# Tx_power.net
KiCad netlist of a schematic drawn in Altium Designer
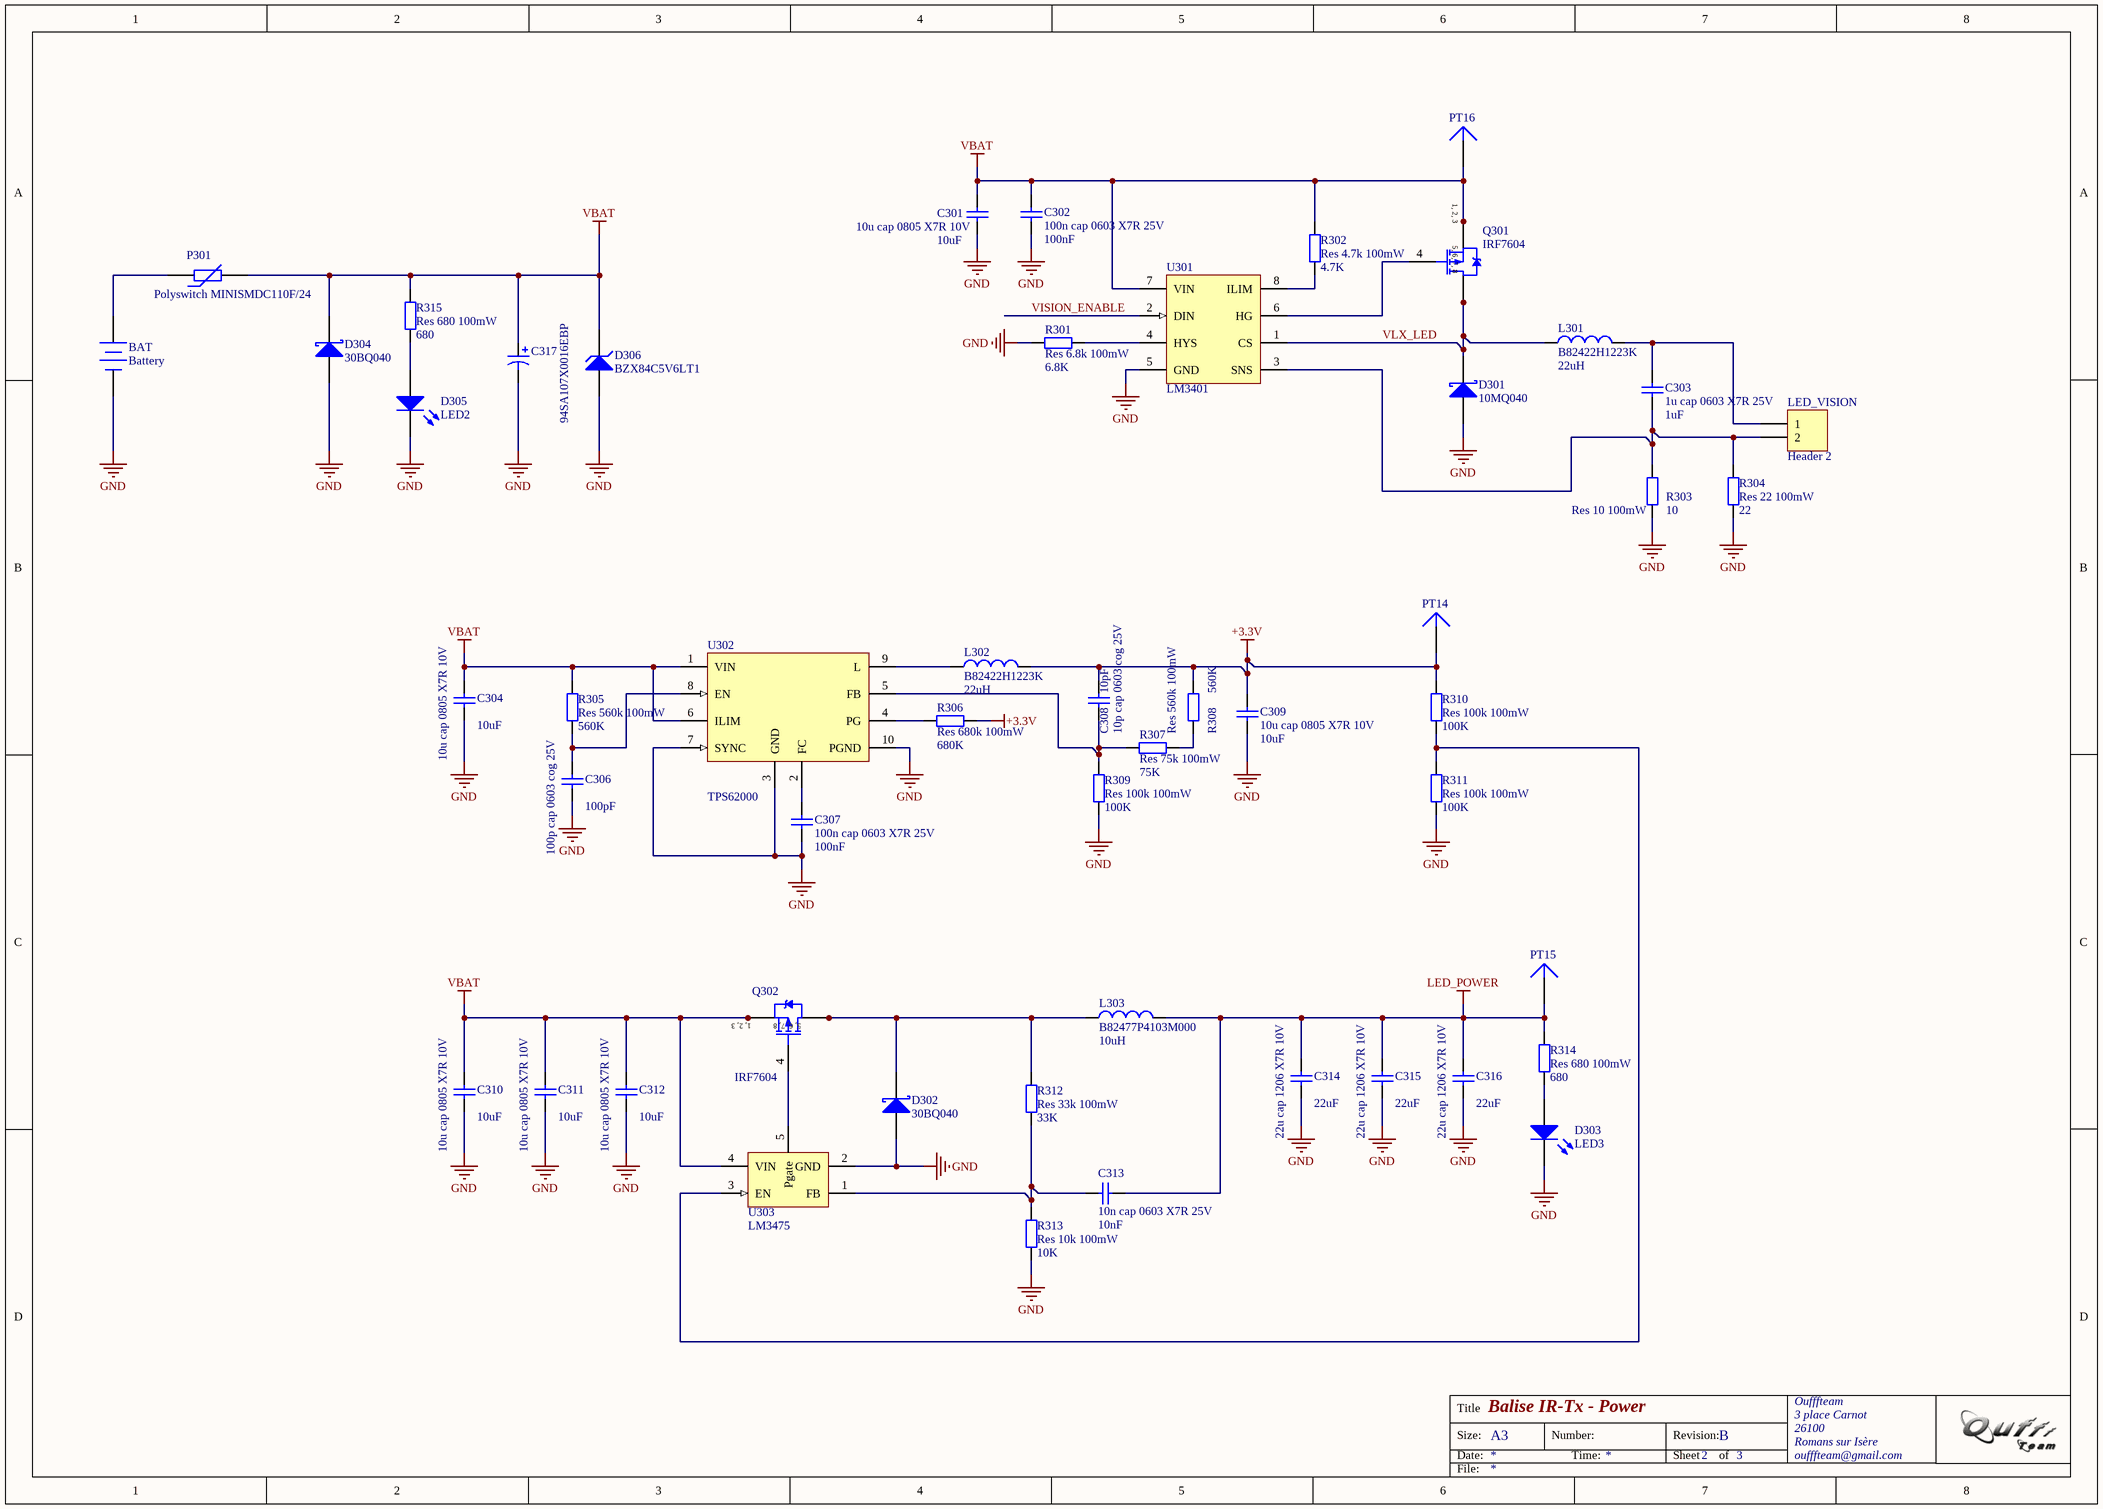
[diagram p0: Tx_power.SchDoc]

(export (version "E")
  (design (tool "Eeschema 10.0.6"))
  (components
    (comp (ref "BAT")
      (value "Battery")
      (footprint "BAT-2")
      (description "Multicell Battery")
      (fields (field (name "PUBLISHER") "Altium Limited"))
      (libsource (lib "Miscellaneous Devices") (part "Battery"))
    )
    (comp (ref "C301")
      (value "10u cap 0805 X7R 10V")
      (footprint "0805")
      (description "Capacitor")
      (fields (field (name "ALTIUM_VALUE") "10uF") (field (name "PUBLISHER") "Altium Limited"))
      (libsource (lib "Miscellaneous Devices") (part "Cap"))
    )
    (comp (ref "C302")
      (value "100n cap 0603 X7R 25V")
      (footprint "0603")
      (description "Capacitor")
      (fields (field (name "ALTIUM_VALUE") "100nF") (field (name "PUBLISHER") "Altium Limited"))
      (libsource (lib "Miscellaneous Devices") (part "Cap"))
    )
    (comp (ref "C303")
      (value "1u cap 0603 X7R 25V")
      (footprint "0603")
      (description "Capacitor")
      (fields (field (name "ALTIUM_VALUE") "1uF") (field (name "PUBLISHER") "Altium Limited"))
      (libsource (lib "Miscellaneous Devices") (part "Cap"))
    )
    (comp (ref "C304")
      (value "10u cap 0805 X7R 10V")
      (footprint "0805")
      (description "Capacitor")
      (fields (field (name "ALTIUM_VALUE") "10uF") (field (name "PUBLISHER") "Altium Limited"))
      (libsource (lib "Miscellaneous Devices") (part "Cap"))
    )
    (comp (ref "C306")
      (value "100p cap 0603 cog 25V")
      (footprint "0603")
      (description "Capacitor")
      (fields (field (name "ALTIUM_VALUE") "100pF") (field (name "PUBLISHER") "Altium Limited"))
      (libsource (lib "Miscellaneous Devices") (part "Cap"))
    )
    (comp (ref "C307")
      (value "100n cap 0603 X7R 25V")
      (footprint "0603")
      (description "Capacitor")
      (fields (field (name "ALTIUM_VALUE") "100nF") (field (name "PUBLISHER") "Altium Limited"))
      (libsource (lib "Miscellaneous Devices") (part "Cap"))
    )
    (comp (ref "C308")
      (value "10p cap 0603 cog 25V")
      (footprint "0603")
      (description "Capacitor")
      (fields (field (name "ALTIUM_VALUE") "10pF") (field (name "PUBLISHER") "Altium Limited"))
      (libsource (lib "Miscellaneous Devices") (part "Cap"))
    )
    (comp (ref "C309")
      (value "10u cap 0805 X7R 10V")
      (footprint "0805")
      (description "Capacitor")
      (fields (field (name "ALTIUM_VALUE") "10uF") (field (name "PUBLISHER") "Altium Limited"))
      (libsource (lib "Miscellaneous Devices") (part "Cap"))
    )
    (comp (ref "C310")
      (value "10u cap 0805 X7R 10V")
      (footprint "0805")
      (description "Capacitor")
      (fields (field (name "ALTIUM_VALUE") "10uF") (field (name "PUBLISHER") "Altium Limited"))
      (libsource (lib "Miscellaneous Devices") (part "Cap"))
    )
    (comp (ref "C311")
      (value "10u cap 0805 X7R 10V")
      (footprint "0805")
      (description "Capacitor")
      (fields (field (name "ALTIUM_VALUE") "10uF") (field (name "PUBLISHER") "Altium Limited"))
      (libsource (lib "Miscellaneous Devices") (part "Cap"))
    )
    (comp (ref "C312")
      (value "10u cap 0805 X7R 10V")
      (footprint "0805")
      (description "Capacitor")
      (fields (field (name "ALTIUM_VALUE") "10uF") (field (name "PUBLISHER") "Altium Limited"))
      (libsource (lib "Miscellaneous Devices") (part "Cap"))
    )
    (comp (ref "C313")
      (value "10n cap 0603 X7R 25V")
      (footprint "0603")
      (description "Capacitor")
      (fields (field (name "ALTIUM_VALUE") "10nF") (field (name "PUBLISHER") "Altium Limited"))
      (libsource (lib "Miscellaneous Devices") (part "Cap"))
    )
    (comp (ref "C314")
      (value "22u cap 1206 X7R 10V")
      (footprint "1206")
      (description "Capacitor")
      (fields (field (name "ALTIUM_VALUE") "22uF") (field (name "PUBLISHER") "Altium Limited"))
      (libsource (lib "Miscellaneous Devices") (part "Cap"))
    )
    (comp (ref "C315")
      (value "22u cap 1206 X7R 10V")
      (footprint "1206")
      (description "Capacitor")
      (fields (field (name "ALTIUM_VALUE") "22uF") (field (name "PUBLISHER") "Altium Limited"))
      (libsource (lib "Miscellaneous Devices") (part "Cap"))
    )
    (comp (ref "C316")
      (value "22u cap 1206 X7R 10V")
      (footprint "1206")
      (description "Capacitor")
      (fields (field (name "ALTIUM_VALUE") "22uF") (field (name "PUBLISHER") "Altium Limited"))
      (libsource (lib "Miscellaneous Devices") (part "Cap"))
    )
    (comp (ref "C317")
      (value "94SA107X0016EBP")
      (footprint "E")
      (description "Solid Aluminum Capacitor with Organic Semiconductor Electrolyte: 100uF, 16V, Bulk Pack")
      (fields (field (name "PUBLISHER") "Altium Limited"))
      (libsource (lib "Vishay Electrolytic Radial-Lead Capacitor") (part "94SA107X0016EBP"))
    )
    (comp (ref "D301")
      (value "10MQ040")
      (footprint "D-64")
      (description "Schottky Rectifier")
      (fields (field (name "PUBLISHER") "Altium Limited"))
      (libsource (lib "IR Rectifier - Schottky") (part "10MQ040"))
    )
    (comp (ref "D302")
      (value "30BQ040")
      (footprint "SMC")
      (description "Schottky Rectifier")
      (fields (field (name "PUBLISHER") "Altium Limited"))
      (libsource (lib "IR Rectifier - Schottky") (part "30BQ040"))
    )
    (comp (ref "D303")
      (value "LED3")
      (footprint "0603")
      (description "Typical BLUE SiC LED")
      (fields (field (name "PUBLISHER") "Altium Limited"))
      (libsource (lib "Miscellaneous Devices") (part "LED3"))
    )
    (comp (ref "D304")
      (value "30BQ040")
      (footprint "SMC")
      (description "Schottky Rectifier")
      (fields (field (name "PUBLISHER") "Altium Limited"))
      (libsource (lib "IR Rectifier - Schottky") (part "30BQ040"))
    )
    (comp (ref "D305")
      (value "LED2")
      (footprint "0603")
      (description "Typical RED, GREEN, YELLOW, AMBER GaAs LED")
      (fields (field (name "PUBLISHER") "Altium Limited"))
      (libsource (lib "Miscellaneous Devices") (part "LED2"))
    )
    (comp (ref "D306")
      (value "BZX84C5V6LT1")
      (footprint "318-07")
      (description "Zener Voltage Regulator Diode")
      (fields (field (name "PUBLISHER") "Altium Limited"))
      (libsource (lib "Motorola Discrete Diode") (part "BZX84C5V6LT1"))
    )
    (comp (ref "L301")
      (value "B82422H1223K")
      (footprint "1210")
      (description "Inductor")
      (fields (field (name "ALTIUM_VALUE") "22uH") (field (name "PUBLISHER") "Altium Limited"))
      (libsource (lib "Miscellaneous Devices") (part "Inductor"))
    )
    (comp (ref "L302")
      (value "B82422H1223K")
      (footprint "1210")
      (description "Inductor")
      (fields (field (name "ALTIUM_VALUE") "22uH") (field (name "PUBLISHER") "Altium Limited"))
      (libsource (lib "Miscellaneous Devices") (part "Inductor"))
    )
    (comp (ref "L303")
      (value "B82477P4103M000")
      (footprint "B82477P4103M000")
      (description "Inductor")
      (fields (field (name "ALTIUM_VALUE") "10uH") (field (name "PUBLISHER") "Altium Limited"))
      (libsource (lib "Miscellaneous Devices") (part "Inductor"))
    )
    (comp (ref "LED_VISION")
      (value "Header 2")
      (footprint "HDR1X2")
      (description "Header, 2-Pin")
      (fields (field (name "PUBLISHER") "Altium Limited"))
      (libsource (lib "Miscellaneous Connectors") (part "Header 2"))
    )
    (comp (ref "P301")
      (value "Polyswitch MINISMDC110F/24")
      (footprint "1812")
      (description "Varistor (Voltage-Sensitive Resistor)")
      (fields (field (name "PUBLISHER") "Altium Limited"))
      (libsource (lib "Miscellaneous Devices") (part "Res Varistor"))
    )
    (comp (ref "PT14")
      (value "Plug")
      (footprint "TP")
      (fields (field (name "PUBLISHER") "Altium Limited"))
      (libsource (lib "Miscellaneous Connectors") (part "Plug"))
    )
    (comp (ref "PT15")
      (value "Plug")
      (footprint "TP")
      (fields (field (name "PUBLISHER") "Altium Limited"))
      (libsource (lib "Miscellaneous Connectors") (part "Plug"))
    )
    (comp (ref "PT16")
      (value "Plug")
      (footprint "TP")
      (fields (field (name "PUBLISHER") "Altium Limited"))
      (libsource (lib "Miscellaneous Connectors") (part "Plug"))
    )
    (comp (ref "Q301")
      (value "IRF7604")
      (footprint "Micro8")
      (description "HEXFET Power MOSFET")
      (fields (field (name "PUBLISHER") "Altium Limited"))
      (libsource (lib "IR Discrete MOSFET - Power") (part "IRF7604"))
    )
    (comp (ref "Q302")
      (value "IRF7604")
      (footprint "Micro8")
      (description "HEXFET Power MOSFET")
      (fields (field (name "PUBLISHER") "Altium Limited"))
      (libsource (lib "IR Discrete MOSFET - Power") (part "IRF7604"))
    )
    (comp (ref "R301")
      (value "Res 6.8k 100mW")
      (footprint "0603")
      (description "Resistor")
      (fields (field (name "ALTIUM_VALUE") "6.8K") (field (name "PUBLISHER") "Altium Limited"))
      (libsource (lib "") (part "Res2_1"))
    )
    (comp (ref "R302")
      (value "Res 4.7k 100mW")
      (footprint "0603")
      (description "Resistor")
      (fields (field (name "ALTIUM_VALUE") "4.7K") (field (name "PUBLISHER") "Altium Limited"))
      (libsource (lib "Miscellaneous Devices") (part "Res2"))
    )
    (comp (ref "R303")
      (value "Res 10 100mW")
      (footprint "0603")
      (description "Resistor")
      (fields (field (name "ALTIUM_VALUE") "10") (field (name "PUBLISHER") "Altium Limited"))
      (libsource (lib "Miscellaneous Devices") (part "Res2"))
    )
    (comp (ref "R304")
      (value "Res 22 100mW")
      (footprint "0603")
      (description "Resistor")
      (fields (field (name "ALTIUM_VALUE") "22") (field (name "PUBLISHER") "Altium Limited"))
      (libsource (lib "Miscellaneous Devices") (part "Res2"))
    )
    (comp (ref "R305")
      (value "Res 560k 100mW")
      (footprint "0603")
      (description "Resistor")
      (fields (field (name "ALTIUM_VALUE") "560K") (field (name "PUBLISHER") "Altium Limited"))
      (libsource (lib "Miscellaneous Devices") (part "Res2"))
    )
    (comp (ref "R306")
      (value "Res 680k 100mW")
      (footprint "0603")
      (description "Resistor")
      (fields (field (name "ALTIUM_VALUE") "680K") (field (name "PUBLISHER") "Altium Limited"))
      (libsource (lib "") (part "Res2_1"))
    )
    (comp (ref "R307")
      (value "Res 75k 100mW")
      (footprint "0603")
      (description "Resistor")
      (fields (field (name "ALTIUM_VALUE") "75K") (field (name "PUBLISHER") "Altium Limited"))
      (libsource (lib "") (part "Res2_1"))
    )
    (comp (ref "R308")
      (value "Res 560k 100mW")
      (footprint "0603")
      (description "Resistor")
      (fields (field (name "ALTIUM_VALUE") "560K") (field (name "PUBLISHER") "Altium Limited"))
      (libsource (lib "Miscellaneous Devices") (part "Res2"))
    )
    (comp (ref "R309")
      (value "Res 100k 100mW")
      (footprint "0603")
      (description "Resistor")
      (fields (field (name "ALTIUM_VALUE") "100K") (field (name "PUBLISHER") "Altium Limited"))
      (libsource (lib "Miscellaneous Devices") (part "Res2"))
    )
    (comp (ref "R310")
      (value "Res 100k 100mW")
      (footprint "0603")
      (description "Resistor")
      (fields (field (name "ALTIUM_VALUE") "100K") (field (name "PUBLISHER") "Altium Limited"))
      (libsource (lib "Miscellaneous Devices") (part "Res2"))
    )
    (comp (ref "R311")
      (value "Res 100k 100mW")
      (footprint "0603")
      (description "Resistor")
      (fields (field (name "ALTIUM_VALUE") "100K") (field (name "PUBLISHER") "Altium Limited"))
      (libsource (lib "Miscellaneous Devices") (part "Res2"))
    )
    (comp (ref "R312")
      (value "Res 33k 100mW")
      (footprint "0603")
      (description "Resistor")
      (fields (field (name "ALTIUM_VALUE") "33K") (field (name "PUBLISHER") "Altium Limited"))
      (libsource (lib "Miscellaneous Devices") (part "Res2"))
    )
    (comp (ref "R313")
      (value "Res 10k 100mW")
      (footprint "0603")
      (description "Resistor")
      (fields (field (name "ALTIUM_VALUE") "10K") (field (name "PUBLISHER") "Altium Limited"))
      (libsource (lib "Miscellaneous Devices") (part "Res2"))
    )
    (comp (ref "R314")
      (value "Res 680 100mW")
      (footprint "0603")
      (description "Resistor")
      (fields (field (name "ALTIUM_VALUE") "680") (field (name "PUBLISHER") "Altium Limited"))
      (libsource (lib "Miscellaneous Devices") (part "Res2"))
    )
    (comp (ref "R315")
      (value "Res 680 100mW")
      (footprint "0603")
      (description "Resistor")
      (fields (field (name "ALTIUM_VALUE") "680") (field (name "PUBLISHER") "Altium Limited"))
      (libsource (lib "Miscellaneous Devices") (part "Res2"))
    )
    (comp (ref "U301")
      (value "LM3401")
      (footprint "MSOP8")
      (description "Hysteretic PFET Controller for High Power LED Drive")
      (libsource (lib "Oufff_Lib2") (part "LM3401"))
    )
    (comp (ref "U302")
      (value "TPS62000")
      (footprint "MS10")
      (description "HIGH-EFFICIENCY STEP-DOWN LOW POWER DC-DC CONVERTER")
      (libsource (lib "Oufff_Lib2") (part "TPS6200x"))
    )
    (comp (ref "U303")
      (value "LM3475")
      (footprint "SOT23-5")
      (description "Hysteretic PFET Buck Controller")
      (libsource (lib "Oufff_Lib2") (part "LM3475"))
    )
  )
  (nets
    (net (code "1") (name "+3.3V") (class "Default")
      (node (ref "C308") (pin "2") (pinfunction "2_2") (pintype "passive"))
      (node (ref "C309") (pin "2") (pinfunction "2_2") (pintype "passive"))
      (node (ref "L302") (pin "2") (pinfunction "2_2") (pintype "passive"))
      (node (ref "PT14") (pin "1") (pinfunction "1_1") (pintype "passive"))
      (node (ref "R306") (pin "2") (pinfunction "2_2") (pintype "passive"))
      (node (ref "R308") (pin "2") (pinfunction "2_2") (pintype "passive"))
      (node (ref "R310") (pin "2") (pinfunction "2_2") (pintype "passive"))
    )
    (net (code "2") (name "/VISION_ENABLE") (class "Default")
      (node (ref "U301") (pin "2") (pinfunction "DIN_2") (pintype "input"))
    )
    (net (code "3") (name "/VLX_LED") (class "Default")
      (node (ref "D301") (pin "2") (pinfunction "K_2") (pintype "passive"))
      (node (ref "L301") (pin "1") (pinfunction "1_1") (pintype "passive"))
      (node (ref "Q301") (pin "5") (pinfunction "D_5") (pintype "passive"))
      (node (ref "Q301") (pin "6") (pinfunction "D_6") (pintype "passive"))
      (node (ref "Q301") (pin "7") (pinfunction "D_7") (pintype "passive"))
      (node (ref "Q301") (pin "8") (pinfunction "D_8") (pintype "passive"))
      (node (ref "U301") (pin "1") (pinfunction "CS_1") (pintype "passive"))
    )
    (net (code "4") (name "GND") (class "Default")
      (node (ref "BAT") (pin "2") (pinfunction "-_2") (pintype "passive"))
      (node (ref "C301") (pin "1") (pinfunction "1_1") (pintype "passive"))
      (node (ref "C302") (pin "1") (pinfunction "1_1") (pintype "passive"))
      (node (ref "C304") (pin "1") (pinfunction "1_1") (pintype "passive"))
      (node (ref "C306") (pin "1") (pinfunction "1_1") (pintype "passive"))
      (node (ref "C307") (pin "1") (pinfunction "1_1") (pintype "passive"))
      (node (ref "C309") (pin "1") (pinfunction "1_1") (pintype "passive"))
      (node (ref "C310") (pin "1") (pinfunction "1_1") (pintype "passive"))
      (node (ref "C311") (pin "1") (pinfunction "1_1") (pintype "passive"))
      (node (ref "C312") (pin "1") (pinfunction "1_1") (pintype "passive"))
      (node (ref "C314") (pin "1") (pinfunction "1_1") (pintype "passive"))
      (node (ref "C315") (pin "1") (pinfunction "1_1") (pintype "passive"))
      (node (ref "C316") (pin "1") (pinfunction "1_1") (pintype "passive"))
      (node (ref "C317") (pin "2") (pinfunction "2_2") (pintype "passive"))
      (node (ref "D301") (pin "1") (pinfunction "A_1") (pintype "passive"))
      (node (ref "D302") (pin "1") (pinfunction "A_1") (pintype "passive"))
      (node (ref "D303") (pin "2") (pinfunction "K_2") (pintype "passive"))
      (node (ref "D304") (pin "1") (pinfunction "A_1") (pintype "passive"))
      (node (ref "D305") (pin "2") (pinfunction "K_2") (pintype "passive"))
      (node (ref "D306") (pin "1") (pinfunction "A_1") (pintype "passive"))
      (node (ref "R301") (pin "1") (pinfunction "1_1") (pintype "passive"))
      (node (ref "R303") (pin "1") (pinfunction "1_1") (pintype "passive"))
      (node (ref "R304") (pin "1") (pinfunction "1_1") (pintype "passive"))
      (node (ref "R309") (pin "1") (pinfunction "1_1") (pintype "passive"))
      (node (ref "R311") (pin "1") (pinfunction "1_1") (pintype "passive"))
      (node (ref "R313") (pin "1") (pinfunction "1_1") (pintype "passive"))
      (node (ref "U301") (pin "5") (pinfunction "GND_5") (pintype "power_in"))
      (node (ref "U302") (pin "10") (pinfunction "PGND_10") (pintype "power_in"))
      (node (ref "U302") (pin "3") (pinfunction "GND_3") (pintype "power_in"))
      (node (ref "U302") (pin "7") (pinfunction "SYNC_7") (pintype "input"))
      (node (ref "U303") (pin "2") (pinfunction "GND_2") (pintype "power_in"))
    )
    (net (code "5") (name "LED_POWER") (class "Default")
      (node (ref "C313") (pin "2") (pinfunction "2_2") (pintype "passive"))
      (node (ref "C314") (pin "2") (pinfunction "2_2") (pintype "passive"))
      (node (ref "C315") (pin "2") (pinfunction "2_2") (pintype "passive"))
      (node (ref "C316") (pin "2") (pinfunction "2_2") (pintype "passive"))
      (node (ref "L303") (pin "2") (pinfunction "2_2") (pintype "passive"))
      (node (ref "PT15") (pin "1") (pinfunction "1_1") (pintype "passive"))
      (node (ref "R314") (pin "2") (pinfunction "2_2") (pintype "passive"))
    )
    (net (code "6") (name "Net-(BAT-+)") (class "Default")
      (node (ref "BAT") (pin "1") (pinfunction "+_1") (pintype "passive"))
      (node (ref "P301") (pin "1") (pinfunction "1_1") (pintype "passive"))
    )
    (net (code "7") (name "Net-(C303-Pad2)") (class "Default")
      (node (ref "C303") (pin "2") (pinfunction "2_2") (pintype "passive"))
      (node (ref "L301") (pin "2") (pinfunction "2_2") (pintype "passive"))
      (node (ref "LED_VISION") (pin "1") (pinfunction "1_1") (pintype "passive"))
    )
    (net (code "8") (name "Net-(D302-K)") (class "Default")
      (node (ref "D302") (pin "2") (pinfunction "K_2") (pintype "passive"))
      (node (ref "L303") (pin "1") (pinfunction "1_1") (pintype "passive"))
      (node (ref "Q302") (pin "5") (pinfunction "D_5") (pintype "passive"))
      (node (ref "Q302") (pin "6") (pinfunction "D_6") (pintype "passive"))
      (node (ref "Q302") (pin "7") (pinfunction "D_7") (pintype "passive"))
      (node (ref "Q302") (pin "8") (pinfunction "D_8") (pintype "passive"))
      (node (ref "R312") (pin "2") (pinfunction "2_2") (pintype "passive"))
    )
    (net (code "9") (name "Net-(D303-A)") (class "Default")
      (node (ref "D303") (pin "1") (pinfunction "A_1") (pintype "passive"))
      (node (ref "R314") (pin "1") (pinfunction "1_1") (pintype "passive"))
    )
    (net (code "10") (name "Net-(D305-A)") (class "Default")
      (node (ref "D305") (pin "1") (pinfunction "A_1") (pintype "passive"))
      (node (ref "R315") (pin "1") (pinfunction "1_1") (pintype "passive"))
    )
    (net (code "11") (name "Net-(Q301-G)") (class "Default")
      (node (ref "Q301") (pin "4") (pinfunction "G_4") (pintype "passive"))
      (node (ref "U301") (pin "6") (pinfunction "HG_6") (pintype "passive"))
    )
    (net (code "12") (name "Net-(Q302-G)") (class "Default")
      (node (ref "Q302") (pin "4") (pinfunction "G_4") (pintype "passive"))
      (node (ref "U303") (pin "5") (pinfunction "Pgate_5") (pintype "power_in"))
    )
    (net (code "13") (name "Net-(R307-Pad2)") (class "Default")
      (node (ref "R307") (pin "2") (pinfunction "2_2") (pintype "passive"))
      (node (ref "R308") (pin "1") (pinfunction "1_1") (pintype "passive"))
    )
    (net (code "14") (name "Net-(U301-HYS)") (class "Default")
      (node (ref "R301") (pin "2") (pinfunction "2_2") (pintype "passive"))
      (node (ref "U301") (pin "4") (pinfunction "HYS_4") (pintype "passive"))
    )
    (net (code "15") (name "Net-(U301-ILIM)") (class "Default")
      (node (ref "R302") (pin "1") (pinfunction "1_1") (pintype "passive"))
      (node (ref "U301") (pin "8") (pinfunction "ILIM_8") (pintype "passive"))
    )
    (net (code "16") (name "Net-(U301-SNS)") (class "Default")
      (node (ref "C303") (pin "1") (pinfunction "1_1") (pintype "passive"))
      (node (ref "LED_VISION") (pin "2") (pinfunction "2_2") (pintype "passive"))
      (node (ref "R303") (pin "2") (pinfunction "2_2") (pintype "passive"))
      (node (ref "R304") (pin "2") (pinfunction "2_2") (pintype "passive"))
      (node (ref "U301") (pin "3") (pinfunction "SNS_3") (pintype "passive"))
    )
    (net (code "17") (name "Net-(U302-EN)") (class "Default")
      (node (ref "C306") (pin "2") (pinfunction "2_2") (pintype "passive"))
      (node (ref "R305") (pin "1") (pinfunction "1_1") (pintype "passive"))
      (node (ref "U302") (pin "8") (pinfunction "EN_8") (pintype "input"))
    )
    (net (code "18") (name "Net-(U302-FB)") (class "Default")
      (node (ref "C308") (pin "1") (pinfunction "1_1") (pintype "passive"))
      (node (ref "R307") (pin "1") (pinfunction "1_1") (pintype "passive"))
      (node (ref "R309") (pin "2") (pinfunction "2_2") (pintype "passive"))
      (node (ref "U302") (pin "5") (pinfunction "FB_5") (pintype "passive"))
    )
    (net (code "19") (name "Net-(U302-FC)") (class "Default")
      (node (ref "C307") (pin "2") (pinfunction "2_2") (pintype "passive"))
      (node (ref "U302") (pin "2") (pinfunction "FC_2") (pintype "passive"))
    )
    (net (code "20") (name "Net-(U302-L)") (class "Default")
      (node (ref "L302") (pin "1") (pinfunction "1_1") (pintype "passive"))
      (node (ref "U302") (pin "9") (pinfunction "L_9") (pintype "power_in"))
    )
    (net (code "21") (name "Net-(U302-PG)") (class "Default")
      (node (ref "R306") (pin "1") (pinfunction "1_1") (pintype "passive"))
      (node (ref "U302") (pin "4") (pinfunction "PG_4") (pintype "open_collector"))
    )
    (net (code "22") (name "Net-(U303-EN)") (class "Default")
      (node (ref "R310") (pin "1") (pinfunction "1_1") (pintype "passive"))
      (node (ref "R311") (pin "2") (pinfunction "2_2") (pintype "passive"))
      (node (ref "U303") (pin "3") (pinfunction "EN_3") (pintype "input"))
    )
    (net (code "23") (name "Net-(U303-FB)") (class "Default")
      (node (ref "C313") (pin "1") (pinfunction "1_1") (pintype "passive"))
      (node (ref "R312") (pin "1") (pinfunction "1_1") (pintype "passive"))
      (node (ref "R313") (pin "2") (pinfunction "2_2") (pintype "passive"))
      (node (ref "U303") (pin "1") (pinfunction "FB_1") (pintype "passive"))
    )
    (net (code "24") (name "VBAT") (class "Default")
      (node (ref "C301") (pin "2") (pinfunction "2_2") (pintype "passive"))
      (node (ref "C302") (pin "2") (pinfunction "2_2") (pintype "passive"))
      (node (ref "C304") (pin "2") (pinfunction "2_2") (pintype "passive"))
      (node (ref "C310") (pin "2") (pinfunction "2_2") (pintype "passive"))
      (node (ref "C311") (pin "2") (pinfunction "2_2") (pintype "passive"))
      (node (ref "C312") (pin "2") (pinfunction "2_2") (pintype "passive"))
      (node (ref "C317") (pin "1") (pinfunction "1_1") (pintype "passive"))
      (node (ref "D304") (pin "2") (pinfunction "K_2") (pintype "passive"))
      (node (ref "D306") (pin "3") (pinfunction "K_3") (pintype "passive"))
      (node (ref "P301") (pin "2") (pinfunction "2_2") (pintype "passive"))
      (node (ref "PT16") (pin "1") (pinfunction "1_1") (pintype "passive"))
      (node (ref "Q301") (pin "1") (pinfunction "S_1") (pintype "passive"))
      (node (ref "Q301") (pin "2") (pinfunction "S_2") (pintype "passive"))
      (node (ref "Q301") (pin "3") (pinfunction "S_3") (pintype "passive"))
      (node (ref "Q302") (pin "1") (pinfunction "S_1") (pintype "passive"))
      (node (ref "Q302") (pin "2") (pinfunction "S_2") (pintype "passive"))
      (node (ref "Q302") (pin "3") (pinfunction "S_3") (pintype "passive"))
      (node (ref "R302") (pin "2") (pinfunction "2_2") (pintype "passive"))
      (node (ref "R305") (pin "2") (pinfunction "2_2") (pintype "passive"))
      (node (ref "R315") (pin "2") (pinfunction "2_2") (pintype "passive"))
      (node (ref "U301") (pin "7") (pinfunction "VIN_7") (pintype "power_in"))
      (node (ref "U302") (pin "1") (pinfunction "VIN_1") (pintype "power_in"))
      (node (ref "U302") (pin "6") (pinfunction "ILIM_6") (pintype "passive"))
      (node (ref "U303") (pin "4") (pinfunction "VIN_4") (pintype "power_in"))
    )
  )
)
